# Encoder.net
KiCad netlist of a schematic drawn in Altium Designer
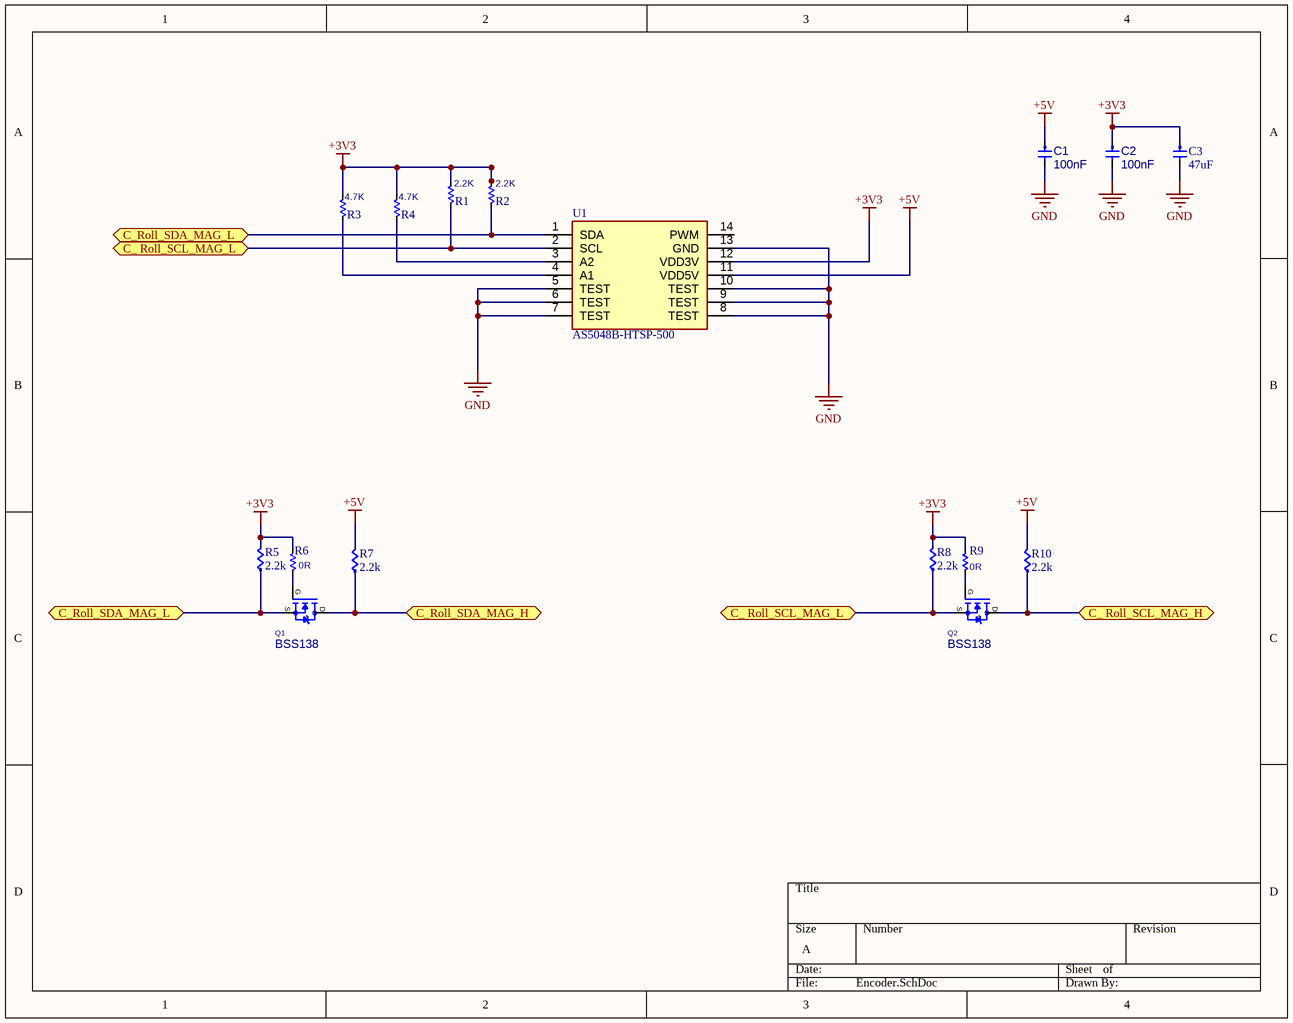
[diagram p0: Encoder.SchDoc]

(export (version "E")
  (design (tool "Eeschema 10.0.6"))
  (components
    (comp (ref "C1")
      (value "C0603C104M5RACTU")
      (footprint "CAP0603")
      (description "CAP CER 0.1UF 50V X7R 0603")
      (fields (field (name "TOLERANCE") "20%") (field (name "CAPACITANCE") "100nF"))
      (libsource (lib "RTR") (part "CMP-00691-1"))
    )
    (comp (ref "C2")
      (value "C0603C104M5RACTU")
      (footprint "CAP0603")
      (description "CAP CER 0.1UF 50V X7R 0603")
      (fields (field (name "TOLERANCE") "20%") (field (name "CAPACITANCE") "100nF"))
      (libsource (lib "RTR") (part "CMP-00691-1"))
    )
    (comp (ref "C3")
      (value "CL21A476MQYNNNE")
      (footprint "CAP0805")
      (description "CAP CER 47UF 6.3V X5R 0805")
      (fields (field (name "TOLERANCE") "20%") (field (name "CAPACITANCE") "47uF"))
      (libsource (lib "RTR") (part "885012107014"))
    )
    (comp (ref "Q1")
      (value "BSS138")
      (footprint "BSS138")
      (description "N-Channel 50 V 220mA (Ta) 350mW (Ta) Surface Mount SOT-23-3")
      (libsource (lib "RTR") (part "BSS138"))
    )
    (comp (ref "Q2")
      (value "BSS138")
      (footprint "BSS138")
      (description "N-Channel 50 V 220mA (Ta) 350mW (Ta) Surface Mount SOT-23-3")
      (libsource (lib "RTR") (part "BSS138"))
    )
    (comp (ref "R1")
      (value "2.2K")
      (footprint "RES0603")
      (description "RES 0805")
      (fields (field (name "MP") "add later") (field (name "Comment") "RES0603"))
      (libsource (lib "RTR") (part "RES0603"))
    )
    (comp (ref "R2")
      (value "2.2K")
      (footprint "RES0603")
      (description "RES 0805")
      (fields (field (name "MP") "add later") (field (name "Comment") "RES0603"))
      (libsource (lib "RTR") (part "RES0603"))
    )
    (comp (ref "R3")
      (value "4.7K")
      (footprint "RES0603")
      (description "RES 0805")
      (fields (field (name "MP") "add later") (field (name "Comment") "RES0603"))
      (libsource (lib "RTR") (part "RES0603"))
    )
    (comp (ref "R4")
      (value "4.7K")
      (footprint "RES0603")
      (description "RES 0805")
      (fields (field (name "MP") "add later") (field (name "Comment") "RES0603"))
      (libsource (lib "RTR") (part "RES0603"))
    )
    (comp (ref "R5")
      (value "2.2k")
      (footprint "RES0603")
      (description "Res Thick Film 0603 2.2K Ohm 1% 0.1W(1/10W) +/-100ppm/C Epoxy Pad SMD T/R")
      (fields
        (field (name "MANUFACTURER") "Yageo Group")
        (field (name "MANUFACTURER PART NUMBER") "RC0603FR-072K2L")
      )
      (libsource (lib "RTR") (part "RC0603FR-072K2L"))
    )
    (comp (ref "R6")
      (value "0R")
      (footprint "RES0603")
      (description "RES 0805")
      (fields (field (name "MP") "add later") (field (name "Comment") "RES0603"))
      (libsource (lib "RTR") (part "RES0603"))
    )
    (comp (ref "R7")
      (value "2.2k")
      (footprint "RES0603")
      (description "Res Thick Film 0603 2.2K Ohm 1% 0.1W(1/10W) +/-100ppm/C Epoxy Pad SMD T/R")
      (fields
        (field (name "MANUFACTURER") "Yageo Group")
        (field (name "MANUFACTURER PART NUMBER") "RC0603FR-072K2L")
      )
      (libsource (lib "RTR") (part "RC0603FR-072K2L"))
    )
    (comp (ref "R8")
      (value "2.2k")
      (footprint "RES0603")
      (description "Res Thick Film 0603 2.2K Ohm 1% 0.1W(1/10W) +/-100ppm/C Epoxy Pad SMD T/R")
      (fields
        (field (name "MANUFACTURER") "Yageo Group")
        (field (name "MANUFACTURER PART NUMBER") "RC0603FR-072K2L")
      )
      (libsource (lib "RTR") (part "RC0603FR-072K2L"))
    )
    (comp (ref "R9")
      (value "0R")
      (footprint "RES0603")
      (description "RES 0805")
      (fields (field (name "MP") "add later") (field (name "Comment") "RES0603"))
      (libsource (lib "RTR") (part "RES0603"))
    )
    (comp (ref "R10")
      (value "2.2k")
      (footprint "RES0603")
      (description "Res Thick Film 0603 2.2K Ohm 1% 0.1W(1/10W) +/-100ppm/C Epoxy Pad SMD T/R")
      (fields
        (field (name "MANUFACTURER") "Yageo Group")
        (field (name "MANUFACTURER PART NUMBER") "RC0603FR-072K2L")
      )
      (libsource (lib "RTR") (part "RC0603FR-072K2L"))
    )
    (comp (ref "U1")
      (value "AS5048B-HTSP-500")
      (footprint "AS5048B-HTSP-500")
      (description "Hall Effect Sensor Angle External Magnet, Not Included Gull Wing")
      (libsource (lib "RTR") (part "AS5048B-HTSP-500"))
    )
  )
  (nets
    (net (code "1") (name "+3V3") (class "Default")
      (node (ref "C2") (pin "1") (pinfunction "1_1") (pintype "passive"))
      (node (ref "C3") (pin "1") (pinfunction "1_1") (pintype "passive"))
      (node (ref "R1") (pin "1") (pinfunction "1_1") (pintype "passive"))
      (node (ref "R2") (pin "1") (pinfunction "1_1") (pintype "passive"))
      (node (ref "R3") (pin "1") (pinfunction "1_1") (pintype "passive"))
      (node (ref "R4") (pin "1") (pinfunction "1_1") (pintype "passive"))
      (node (ref "R5") (pin "2") (pinfunction "2_2") (pintype "passive"))
      (node (ref "R6") (pin "2") (pinfunction "2_2") (pintype "passive"))
      (node (ref "R8") (pin "2") (pinfunction "2_2") (pintype "passive"))
      (node (ref "R9") (pin "2") (pinfunction "2_2") (pintype "passive"))
      (node (ref "U1") (pin "12") (pinfunction "VDD3V_12") (pintype "passive"))
    )
    (net (code "2") (name "+5V") (class "Default")
      (node (ref "C1") (pin "1") (pinfunction "1_1") (pintype "passive"))
      (node (ref "R10") (pin "2") (pinfunction "2_2") (pintype "passive"))
      (node (ref "R7") (pin "2") (pinfunction "2_2") (pintype "passive"))
      (node (ref "U1") (pin "11") (pinfunction "VDD5V_11") (pintype "passive"))
    )
    (net (code "3") (name "/C_ Roll_SCL_MAG_H") (class "Default")
      (node (ref "Q2") (pin "3") (pinfunction "D_3") (pintype "passive"))
      (node (ref "R10") (pin "1") (pinfunction "1_1") (pintype "passive"))
    )
    (net (code "4") (name "/C_ Roll_SCL_MAG_L") (class "Default")
      (node (ref "Q2") (pin "2") (pinfunction "S_2") (pintype "passive"))
      (node (ref "R1") (pin "2") (pinfunction "2_2") (pintype "passive"))
      (node (ref "R8") (pin "1") (pinfunction "1_1") (pintype "passive"))
      (node (ref "U1") (pin "2") (pinfunction "SCL_2") (pintype "passive"))
    )
    (net (code "5") (name "/C_Roll_SDA_MAG_H") (class "Default")
      (node (ref "Q1") (pin "3") (pinfunction "D_3") (pintype "passive"))
      (node (ref "R7") (pin "1") (pinfunction "1_1") (pintype "passive"))
    )
    (net (code "6") (name "/C_Roll_SDA_MAG_L") (class "Default")
      (node (ref "Q1") (pin "2") (pinfunction "S_2") (pintype "passive"))
      (node (ref "R2") (pin "2") (pinfunction "2_2") (pintype "passive"))
      (node (ref "R5") (pin "1") (pinfunction "1_1") (pintype "passive"))
      (node (ref "U1") (pin "1") (pinfunction "SDA_1") (pintype "passive"))
    )
    (net (code "7") (name "GND") (class "Default")
      (node (ref "C1") (pin "2") (pinfunction "2_2") (pintype "passive"))
      (node (ref "C2") (pin "2") (pinfunction "2_2") (pintype "passive"))
      (node (ref "C3") (pin "2") (pinfunction "2_2") (pintype "passive"))
      (node (ref "U1") (pin "10") (pinfunction "TEST_10") (pintype "passive"))
      (node (ref "U1") (pin "13") (pinfunction "GND_13") (pintype "passive"))
      (node (ref "U1") (pin "5") (pinfunction "TEST_5") (pintype "passive"))
      (node (ref "U1") (pin "6") (pinfunction "TEST_6") (pintype "passive"))
      (node (ref "U1") (pin "7") (pinfunction "TEST_7") (pintype "passive"))
      (node (ref "U1") (pin "8") (pinfunction "TEST_8") (pintype "passive"))
      (node (ref "U1") (pin "9") (pinfunction "TEST_9") (pintype "passive"))
    )
    (net (code "8") (name "Net-(Q1-G)") (class "Default")
      (node (ref "Q1") (pin "1") (pinfunction "G_1") (pintype "passive"))
      (node (ref "R6") (pin "1") (pinfunction "1_1") (pintype "passive"))
    )
    (net (code "9") (name "Net-(Q2-G)") (class "Default")
      (node (ref "Q2") (pin "1") (pinfunction "G_1") (pintype "passive"))
      (node (ref "R9") (pin "1") (pinfunction "1_1") (pintype "passive"))
    )
    (net (code "10") (name "Net-(U1-A1)") (class "Default")
      (node (ref "R3") (pin "2") (pinfunction "2_2") (pintype "passive"))
      (node (ref "U1") (pin "4") (pinfunction "A1_4") (pintype "passive"))
    )
    (net (code "11") (name "Net-(U1-A2)") (class "Default")
      (node (ref "R4") (pin "2") (pinfunction "2_2") (pintype "passive"))
      (node (ref "U1") (pin "3") (pinfunction "A2_3") (pintype "passive"))
    )
    (net (code "12") (name "unconnected-(U1-PWM-Pad14)") (class "Default")
      (node (ref "U1") (pin "14") (pinfunction "PWM_14") (pintype "passive"))
    )
  )
)
